# BeagleQ-v03_1.net
KiCad netlist of a schematic drawn in EAGLE
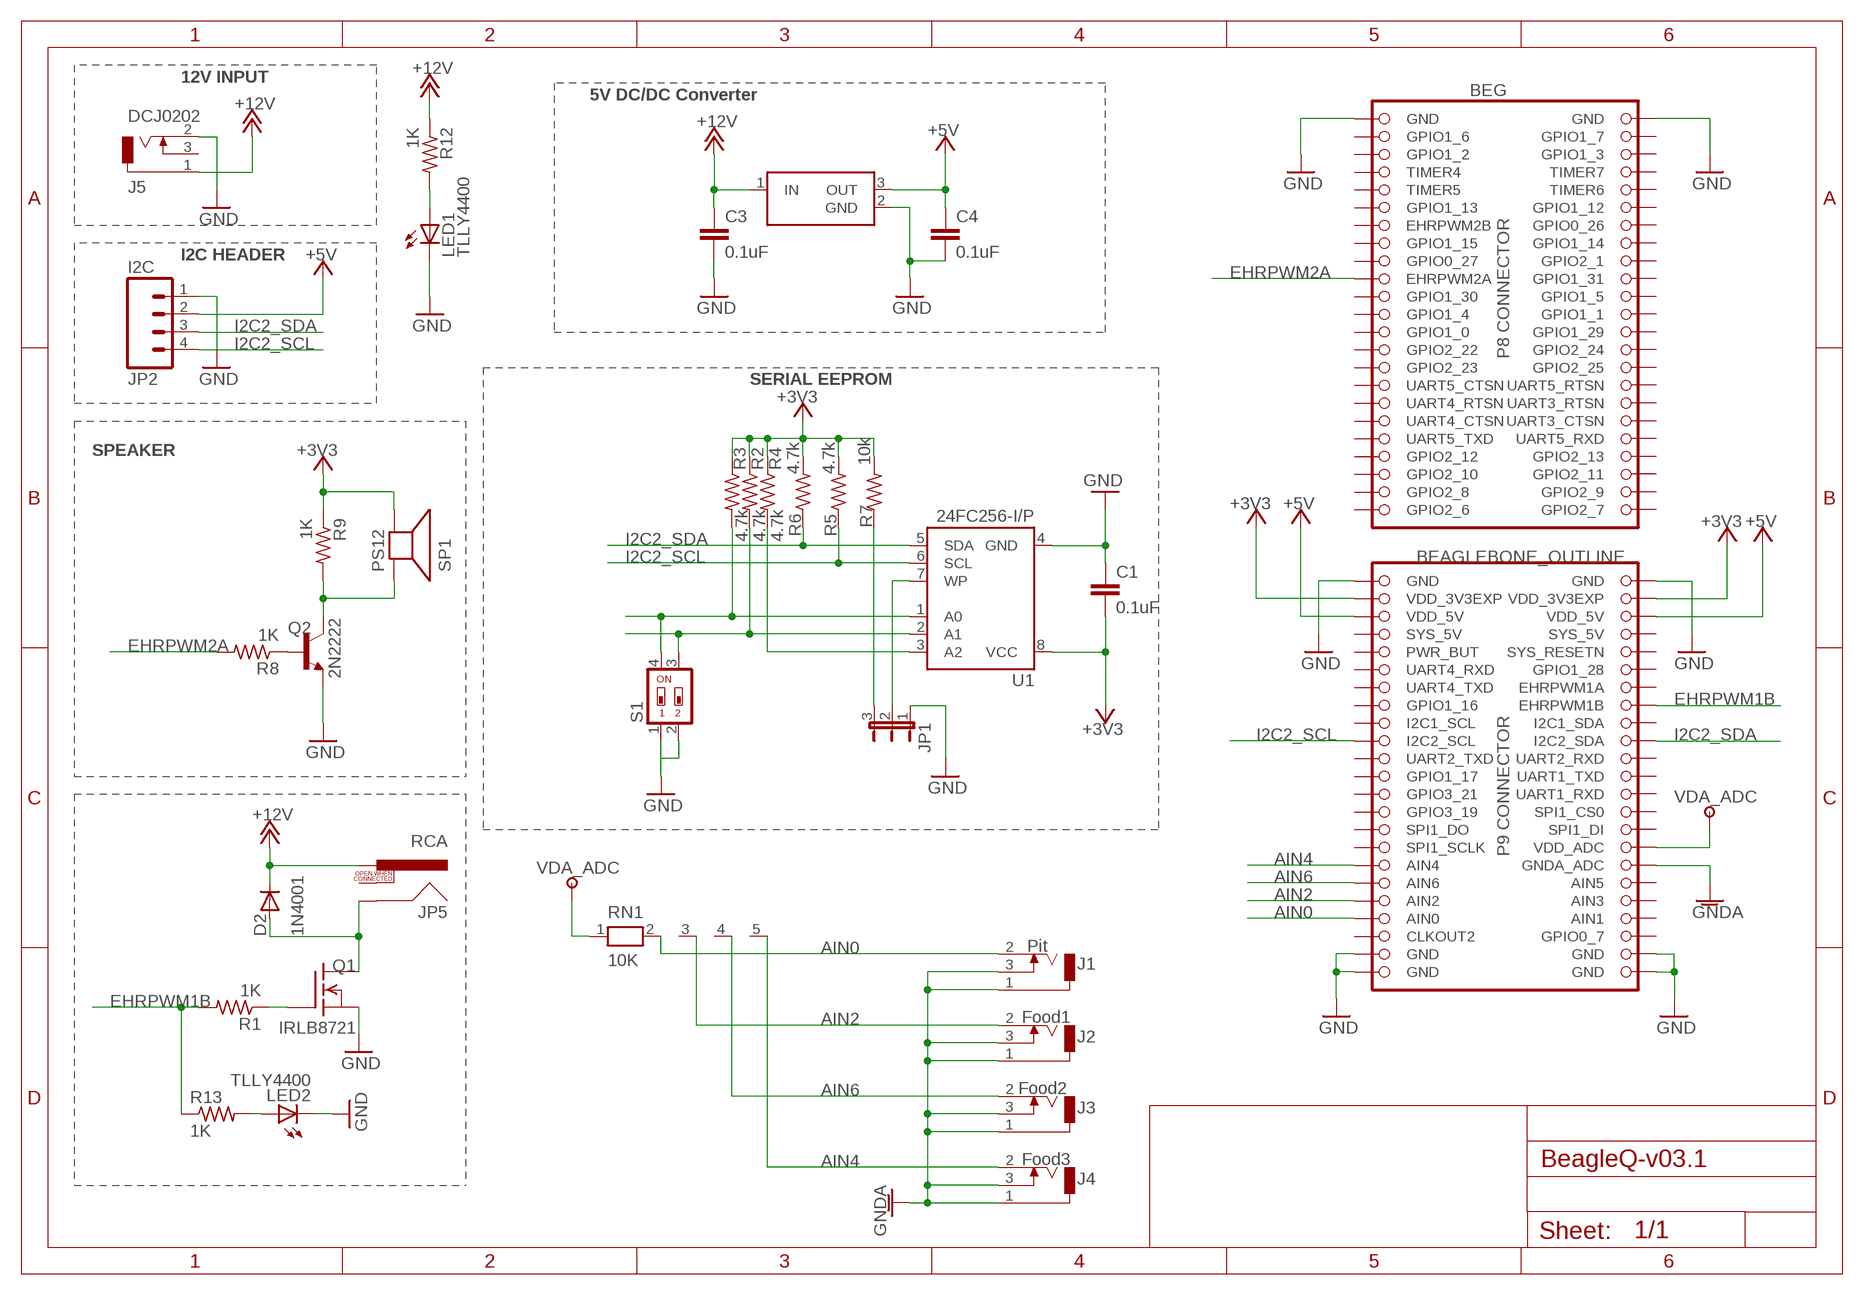
[diagram p0: schematic, sheet 1]

(export (version "E")
  (design (tool "Eeschema 10.0.6"))
  (components
    (comp (ref "BEG")
      (value "BEAGLEBONE_OUTLINE")
      (footprint "eagle-import:BEAGLEBONE_SHIELD")
      (libsource (lib "eagle-import") (part "BEAGLEBONE_OUTLINE"))
    )
    (comp (ref "C1")
      (value "0.1uF")
      (footprint "eagle-import:C2.5-2")
      (libsource (lib "eagle-import") (part "C2.5/2"))
    )
    (comp (ref "C3")
      (value "0.1uF")
      (footprint "eagle-import:C2.5-2")
      (libsource (lib "eagle-import") (part "C2.5/2"))
    )
    (comp (ref "C4")
      (value "0.1uF")
      (footprint "eagle-import:C2.5-2")
      (libsource (lib "eagle-import") (part "C2.5/2"))
    )
    (comp (ref "D2")
      (value "1N4001")
      (footprint "eagle-import:DO41-10")
      (libsource (lib "eagle-import") (part "1N4004"))
    )
    (comp (ref "J1")
      (value "Pit")
      (footprint "eagle-import:MJ-2508N")
      (libsource (lib "eagle-import") (part "MJ-2508N"))
    )
    (comp (ref "J2")
      (value "Food1")
      (footprint "eagle-import:MJ-2508N")
      (libsource (lib "eagle-import") (part "MJ-2508N"))
    )
    (comp (ref "J3")
      (value "Food2")
      (footprint "eagle-import:MJ-2508N")
      (libsource (lib "eagle-import") (part "MJ-2508N"))
    )
    (comp (ref "J4")
      (value "Food3")
      (footprint "eagle-import:MJ-2508N")
      (libsource (lib "eagle-import") (part "MJ-2508N"))
    )
    (comp (ref "J5")
      (value "DCJ0202")
      (footprint "eagle-import:DCJ0202")
      (libsource (lib "eagle-import") (part "DCJ0202"))
    )
    (comp (ref "JP1")
      (value "WP")
      (footprint "eagle-import:JP2")
      (libsource (lib "eagle-import") (part "JP2E"))
    )
    (comp (ref "JP2")
      (value "I2C")
      (footprint "eagle-import:1X04")
      (libsource (lib "eagle-import") (part "M04PTH"))
    )
    (comp (ref "JP5")
      (value "RCA")
      (footprint "eagle-import:RCA")
      (libsource (lib "eagle-import") (part "RCA"))
    )
    (comp (ref "LED1")
      (value "TLLY4400")
      (footprint "eagle-import:LED3MM")
      (fields (field (name "MF") "VISHAY SEMICONDUCTOR"))
      (libsource (lib "eagle-import") (part "led_TLLY4400"))
    )
    (comp (ref "LED2")
      (value "TLLY4400")
      (footprint "eagle-import:LED3MM")
      (fields (field (name "MF") "VISHAY SEMICONDUCTOR"))
      (libsource (lib "eagle-import") (part "TLLY4400"))
    )
    (comp (ref "Q1")
      (value "IRLB8721")
      (footprint "eagle-import:TO220")
      (libsource (lib "eagle-import") (part "BUZ10"))
    )
    (comp (ref "Q2")
      (value "2N2222")
      (footprint "eagle-import:TO18")
      (libsource (lib "eagle-import") (part "2N2222"))
    )
    (comp (ref "R1")
      (value "1K")
      (footprint "eagle-import:0207_10")
      (libsource (lib "eagle-import") (part "R-US_0207/10"))
    )
    (comp (ref "R2")
      (value "4.7k")
      (footprint "eagle-import:0207_10")
      (libsource (lib "eagle-import") (part "resistor_R-US_0207/10"))
    )
    (comp (ref "R3")
      (value "4.7k")
      (footprint "eagle-import:0207_10")
      (libsource (lib "eagle-import") (part "resistor_R-US_0207/10"))
    )
    (comp (ref "R4")
      (value "4.7k")
      (footprint "eagle-import:0207_10")
      (libsource (lib "eagle-import") (part "resistor_R-US_0207/10"))
    )
    (comp (ref "R5")
      (value "4.7k")
      (footprint "eagle-import:0207_10")
      (libsource (lib "eagle-import") (part "resistor_R-US_0207/10"))
    )
    (comp (ref "R6")
      (value "4.7k")
      (footprint "eagle-import:0207_10")
      (libsource (lib "eagle-import") (part "resistor_R-US_0207/10"))
    )
    (comp (ref "R7")
      (value "10k")
      (footprint "eagle-import:0207_10")
      (libsource (lib "eagle-import") (part "resistor_R-US_0207/10"))
    )
    (comp (ref "R8")
      (value "1K")
      (footprint "eagle-import:0207_10")
      (libsource (lib "eagle-import") (part "R-US_0207/10"))
    )
    (comp (ref "R9")
      (value "1K")
      (footprint "eagle-import:0207_10")
      (libsource (lib "eagle-import") (part "R-US_0207/10"))
    )
    (comp (ref "R12")
      (value "1K")
      (footprint "eagle-import:0207_10")
      (libsource (lib "eagle-import") (part "resistor_R-US_0207/10"))
    )
    (comp (ref "R13")
      (value "1K")
      (footprint "eagle-import:0207_10")
      (libsource (lib "eagle-import") (part "resistor_R-US_0207/10"))
    )
    (comp (ref "RN1")
      (value "10K")
      (footprint "eagle-import:RN-5")
      (libsource (lib "eagle-import") (part "RN04"))
    )
    (comp (ref "S1")
      (value "SWS002")
      (footprint "eagle-import:SMS-002")
      (libsource (lib "eagle-import") (part "SWS002"))
    )
    (comp (ref "SP1")
      (value "PS12")
      (footprint "eagle-import:PS12")
      (libsource (lib "eagle-import") (part "SPEAKER/PS12"))
    )
    (comp (ref "U1")
      (value "24FC256-I/P")
      (footprint "eagle-import:DIL08")
      (fields (field (name "MPN") "AT24C1024BW-SH-B"))
      (libsource (lib "eagle-import") (part "AT24CP"))
    )
    (comp (ref "U2")
      (value "OKI-78SR")
      (footprint "eagle-import:OKI-78SR")
      (libsource (lib "eagle-import") (part "OKI-78SR"))
    )
  )
  (nets
    (net (code "1") (name "+3V3") (class "Default")
      (node (ref "BEG") (pin "49") (pinfunction "VDD_3V3EXP_49") (pintype "power_in"))
      (node (ref "BEG") (pin "50") (pinfunction "VDD_3V3EXP_50") (pintype "power_in"))
      (node (ref "C1") (pin "2") (pinfunction "2_2") (pintype "passive"))
      (node (ref "R2") (pin "1") (pinfunction "1_1") (pintype "passive"))
      (node (ref "R3") (pin "1") (pinfunction "1_1") (pintype "passive"))
      (node (ref "R4") (pin "1") (pinfunction "1_1") (pintype "passive"))
      (node (ref "R5") (pin "2") (pinfunction "2_2") (pintype "passive"))
      (node (ref "R6") (pin "2") (pinfunction "2_2") (pintype "passive"))
      (node (ref "R7") (pin "2") (pinfunction "2_2") (pintype "passive"))
      (node (ref "R9") (pin "1") (pinfunction "1_1") (pintype "passive"))
      (node (ref "SP1") (pin "P$2") (pinfunction "-_P$2") (pintype "passive"))
      (node (ref "U1") (pin "8") (pinfunction "VCC_8") (pintype "power_in"))
    )
    (net (code "2") (name "+5V") (class "Default")
      (node (ref "BEG") (pin "51") (pinfunction "VDD_5V_51") (pintype "power_in"))
      (node (ref "BEG") (pin "52") (pinfunction "VDD_5V_52") (pintype "power_in"))
      (node (ref "C4") (pin "1") (pinfunction "1_1") (pintype "passive"))
      (node (ref "JP2") (pin "2") (pinfunction "2_2") (pintype "passive"))
      (node (ref "U2") (pin "3") (pinfunction "OUT_3") (pintype "passive"))
    )
    (net (code "3") (name "+12V") (class "Default")
      (node (ref "C3") (pin "1") (pinfunction "1_1") (pintype "passive"))
      (node (ref "D2") (pin "C") (pinfunction "C_C") (pintype "passive"))
      (node (ref "J5") (pin "1") (pinfunction "1_1") (pintype "passive"))
      (node (ref "JP5") (pin "PIN") (pinfunction "PIN_PIN") (pintype "bidirectional"))
      (node (ref "R12") (pin "1") (pinfunction "1_1") (pintype "passive"))
      (node (ref "U2") (pin "1") (pinfunction "IN_1") (pintype "passive"))
    )
    (net (code "4") (name "/AIN0") (class "Default")
      (node (ref "BEG") (pin "85") (pinfunction "AIN0_85") (pintype "power_in"))
      (node (ref "J1") (pin "2") (pinfunction "2_2") (pintype "passive"))
      (node (ref "RN1") (pin "2") (pinfunction "2_2") (pintype "passive"))
    )
    (net (code "5") (name "/AIN2") (class "Default")
      (node (ref "BEG") (pin "83") (pinfunction "AIN2_83") (pintype "passive"))
      (node (ref "J2") (pin "2") (pinfunction "2_2") (pintype "passive"))
      (node (ref "RN1") (pin "3") (pinfunction "3_3") (pintype "passive"))
    )
    (net (code "6") (name "/AIN4") (class "Default")
      (node (ref "BEG") (pin "79") (pinfunction "AIN4_79") (pintype "passive"))
      (node (ref "J4") (pin "2") (pinfunction "2_2") (pintype "passive"))
      (node (ref "RN1") (pin "5") (pinfunction "5_5") (pintype "passive"))
    )
    (net (code "7") (name "/AIN6") (class "Default")
      (node (ref "BEG") (pin "81") (pinfunction "AIN6_81") (pintype "passive"))
      (node (ref "J3") (pin "2") (pinfunction "2_2") (pintype "passive"))
      (node (ref "RN1") (pin "4") (pinfunction "4_4") (pintype "passive"))
    )
    (net (code "8") (name "/EHRPWM1B") (class "Default")
      (node (ref "BEG") (pin "62") (pinfunction "EHRPWM1B_62") (pintype "passive"))
      (node (ref "R1") (pin "2") (pinfunction "2_2") (pintype "passive"))
      (node (ref "R13") (pin "1") (pinfunction "1_1") (pintype "passive"))
    )
    (net (code "9") (name "/EHRPWM2A") (class "Default")
      (node (ref "BEG") (pin "19") (pinfunction "EHRPWM2A_19") (pintype "passive"))
      (node (ref "R8") (pin "2") (pinfunction "2_2") (pintype "passive"))
    )
    (net (code "10") (name "/I2C2_SCL") (class "Default")
      (node (ref "BEG") (pin "65") (pinfunction "I2C2_SCL_65") (pintype "passive"))
      (node (ref "JP2") (pin "4") (pinfunction "4_4") (pintype "passive"))
      (node (ref "R5") (pin "1") (pinfunction "1_1") (pintype "passive"))
      (node (ref "U1") (pin "6") (pinfunction "SCL_6") (pintype "bidirectional"))
    )
    (net (code "11") (name "/I2C2_SDA") (class "Default")
      (node (ref "BEG") (pin "66") (pinfunction "I2C2_SDA_66") (pintype "passive"))
      (node (ref "JP2") (pin "3") (pinfunction "3_3") (pintype "passive"))
      (node (ref "R6") (pin "1") (pinfunction "1_1") (pintype "passive"))
      (node (ref "U1") (pin "5") (pinfunction "SDA_5") (pintype "bidirectional"))
    )
    (net (code "12") (name "/SYS_5V") (class "Default")
      (node (ref "BEG") (pin "53") (pinfunction "SYS_5V_53") (pintype "power_in"))
    )
    (net (code "13") (name "GND") (class "Default")
      (node (ref "BEG") (pin "1") (pinfunction "GND_1") (pintype "power_in"))
      (node (ref "BEG") (pin "2") (pinfunction "GND_2") (pintype "power_in"))
      (node (ref "BEG") (pin "47") (pinfunction "GND_47") (pintype "power_in"))
      (node (ref "BEG") (pin "48") (pinfunction "GND_48") (pintype "power_in"))
      (node (ref "BEG") (pin "89") (pinfunction "GND_89") (pintype "power_in"))
      (node (ref "BEG") (pin "90") (pinfunction "GND_90") (pintype "power_in"))
      (node (ref "BEG") (pin "91") (pinfunction "GND_91") (pintype "power_in"))
      (node (ref "BEG") (pin "92") (pinfunction "GND_92") (pintype "power_in"))
      (node (ref "C1") (pin "1") (pinfunction "1_1") (pintype "passive"))
      (node (ref "C3") (pin "2") (pinfunction "2_2") (pintype "passive"))
      (node (ref "C4") (pin "2") (pinfunction "2_2") (pintype "passive"))
      (node (ref "J5") (pin "2") (pinfunction "3_2") (pintype "passive"))
      (node (ref "JP1") (pin "1") (pinfunction "1_1") (pintype "passive"))
      (node (ref "JP2") (pin "1") (pinfunction "1_1") (pintype "passive"))
      (node (ref "LED1") (pin "K") (pinfunction "C_K") (pintype "passive"))
      (node (ref "LED2") (pin "K") (pinfunction "C_K") (pintype "passive"))
      (node (ref "Q1") (pin "3") (pinfunction "S_3") (pintype "passive"))
      (node (ref "Q1") (pin "4") (pinfunction "S_4") (pintype "passive"))
      (node (ref "Q2") (pin "1") (pinfunction "E_1") (pintype "passive"))
      (node (ref "S1") (pin "1") (pinfunction "1_1") (pintype "passive"))
      (node (ref "S1") (pin "2") (pinfunction "2_2") (pintype "passive"))
      (node (ref "U1") (pin "4") (pinfunction "GND_4") (pintype "power_in"))
      (node (ref "U2") (pin "2") (pinfunction "GND_2") (pintype "passive"))
    )
    (net (code "14") (name "GNDA") (class "Default")
      (node (ref "BEG") (pin "80") (pinfunction "GNDA_ADC_80") (pintype "passive"))
      (node (ref "J1") (pin "1") (pinfunction "1_1") (pintype "passive"))
      (node (ref "J1") (pin "3") (pinfunction "3_3") (pintype "passive"))
      (node (ref "J2") (pin "1") (pinfunction "1_1") (pintype "passive"))
      (node (ref "J2") (pin "3") (pinfunction "3_3") (pintype "passive"))
      (node (ref "J3") (pin "1") (pinfunction "1_1") (pintype "passive"))
      (node (ref "J3") (pin "3") (pinfunction "3_3") (pintype "passive"))
      (node (ref "J4") (pin "1") (pinfunction "1_1") (pintype "passive"))
      (node (ref "J4") (pin "3") (pinfunction "3_3") (pintype "passive"))
    )
    (net (code "15") (name "Net-(JP1-Pad3)") (class "Default")
      (node (ref "JP1") (pin "3") (pinfunction "3_3") (pintype "passive"))
      (node (ref "R7") (pin "1") (pinfunction "1_1") (pintype "passive"))
    )
    (net (code "16") (name "Net-(LED1-PadA)") (class "Default")
      (node (ref "LED1") (pin "A") (pinfunction "A_A") (pintype "passive"))
      (node (ref "R12") (pin "2") (pinfunction "2_2") (pintype "passive"))
    )
    (net (code "17") (name "Net-(LED2-PadA)") (class "Default")
      (node (ref "LED2") (pin "A") (pinfunction "A_A") (pintype "passive"))
      (node (ref "R13") (pin "2") (pinfunction "2_2") (pintype "passive"))
    )
    (net (code "18") (name "Net-(Q1-D)") (class "Default")
      (node (ref "D2") (pin "A") (pinfunction "A_A") (pintype "passive"))
      (node (ref "JP5") (pin "SHELL") (pinfunction "SHELL_SHELL") (pintype "bidirectional"))
      (node (ref "Q1") (pin "2") (pinfunction "D_2") (pintype "passive"))
    )
    (net (code "19") (name "Net-(Q1-G)") (class "Default")
      (node (ref "Q1") (pin "1") (pinfunction "G_1") (pintype "passive"))
      (node (ref "R1") (pin "1") (pinfunction "1_1") (pintype "passive"))
    )
    (net (code "20") (name "Net-(Q2-B)") (class "Default")
      (node (ref "Q2") (pin "2") (pinfunction "B_2") (pintype "passive"))
      (node (ref "R8") (pin "1") (pinfunction "1_1") (pintype "passive"))
    )
    (net (code "21") (name "Net-(Q2-C)") (class "Default")
      (node (ref "Q2") (pin "3") (pinfunction "C_3") (pintype "passive"))
      (node (ref "R9") (pin "2") (pinfunction "2_2") (pintype "passive"))
      (node (ref "SP1") (pin "P$1") (pinfunction "+_P$1") (pintype "passive"))
    )
    (net (code "22") (name "Net-(U1-A0)") (class "Default")
      (node (ref "R3") (pin "2") (pinfunction "2_2") (pintype "passive"))
      (node (ref "S1") (pin "4") (pinfunction "4_4") (pintype "passive"))
      (node (ref "U1") (pin "1") (pinfunction "A0_1") (pintype "input"))
    )
    (net (code "23") (name "Net-(U1-A1)") (class "Default")
      (node (ref "R2") (pin "2") (pinfunction "2_2") (pintype "passive"))
      (node (ref "S1") (pin "3") (pinfunction "3_3") (pintype "passive"))
      (node (ref "U1") (pin "2") (pinfunction "A1_2") (pintype "input"))
    )
    (net (code "24") (name "Net-(U1-A2)") (class "Default")
      (node (ref "R4") (pin "2") (pinfunction "2_2") (pintype "passive"))
      (node (ref "U1") (pin "3") (pinfunction "A2_3") (pintype "input"))
    )
    (net (code "25") (name "Net-(U1-WP)") (class "Default")
      (node (ref "JP1") (pin "2") (pinfunction "2_2") (pintype "passive"))
      (node (ref "U1") (pin "7") (pinfunction "WP_7") (pintype "input"))
    )
    (net (code "26") (name "VDA_ADC") (class "Default")
      (node (ref "BEG") (pin "78") (pinfunction "VDD_ADC_78") (pintype "passive"))
      (node (ref "RN1") (pin "1") (pinfunction "1_1") (pintype "passive"))
    )
    (net (code "27") (name "unconnected-(BEG-AIN1-Pad86)") (class "Default")
      (node (ref "BEG") (pin "86") (pinfunction "AIN1_86") (pintype "passive"))
    )
    (net (code "28") (name "unconnected-(BEG-AIN3-Pad84)") (class "Default")
      (node (ref "BEG") (pin "84") (pinfunction "AIN3_84") (pintype "passive"))
    )
    (net (code "29") (name "unconnected-(BEG-AIN5-Pad82)") (class "Default")
      (node (ref "BEG") (pin "82") (pinfunction "AIN5_82") (pintype "passive"))
    )
    (net (code "30") (name "unconnected-(BEG-CLKOUT2-Pad87)") (class "Default")
      (node (ref "BEG") (pin "87") (pinfunction "CLKOUT2_87") (pintype "input"))
    )
    (net (code "31") (name "unconnected-(BEG-EHRPWM1A-Pad60)") (class "Default")
      (node (ref "BEG") (pin "60") (pinfunction "EHRPWM1A_60") (pintype "passive"))
    )
    (net (code "32") (name "unconnected-(BEG-EHRPWM2B-Pad13)") (class "Default")
      (node (ref "BEG") (pin "13") (pinfunction "EHRPWM2B_13") (pintype "passive"))
    )
    (net (code "33") (name "unconnected-(BEG-GPIO0_7-Pad88)") (class "Default")
      (node (ref "BEG") (pin "88") (pinfunction "GPIO0_7_88") (pintype "passive"))
    )
    (net (code "34") (name "unconnected-(BEG-GPIO0_26-Pad14)") (class "Default")
      (node (ref "BEG") (pin "14") (pinfunction "GPIO0_26_14") (pintype "passive"))
    )
    (net (code "35") (name "unconnected-(BEG-GPIO0_27-Pad17)") (class "Default")
      (node (ref "BEG") (pin "17") (pinfunction "GPIO0_27_17") (pintype "passive"))
    )
    (net (code "36") (name "unconnected-(BEG-GPIO1_0-Pad25)") (class "Default")
      (node (ref "BEG") (pin "25") (pinfunction "GPIO1_0_25") (pintype "passive"))
    )
    (net (code "37") (name "unconnected-(BEG-GPIO1_1-Pad24)") (class "Default")
      (node (ref "BEG") (pin "24") (pinfunction "GPIO1_1_24") (pintype "passive"))
    )
    (net (code "38") (name "unconnected-(BEG-GPIO1_2-Pad5)") (class "Default")
      (node (ref "BEG") (pin "5") (pinfunction "GPIO1_2_5") (pintype "passive"))
    )
    (net (code "39") (name "unconnected-(BEG-GPIO1_3-Pad6)") (class "Default")
      (node (ref "BEG") (pin "6") (pinfunction "GPIO1_3_6") (pintype "passive"))
    )
    (net (code "40") (name "unconnected-(BEG-GPIO1_4-Pad23)") (class "Default")
      (node (ref "BEG") (pin "23") (pinfunction "GPIO1_4_23") (pintype "passive"))
    )
    (net (code "41") (name "unconnected-(BEG-GPIO1_5-Pad22)") (class "Default")
      (node (ref "BEG") (pin "22") (pinfunction "GPIO1_5_22") (pintype "passive"))
    )
    (net (code "42") (name "unconnected-(BEG-GPIO1_6-Pad3)") (class "Default")
      (node (ref "BEG") (pin "3") (pinfunction "GPIO1_6_3") (pintype "passive"))
    )
    (net (code "43") (name "unconnected-(BEG-GPIO1_7-Pad4)") (class "Default")
      (node (ref "BEG") (pin "4") (pinfunction "GPIO1_7_4") (pintype "passive"))
    )
    (net (code "44") (name "unconnected-(BEG-GPIO1_12-Pad12)") (class "Default")
      (node (ref "BEG") (pin "12") (pinfunction "GPIO1_12_12") (pintype "passive"))
    )
    (net (code "45") (name "unconnected-(BEG-GPIO1_13-Pad11)") (class "Default")
      (node (ref "BEG") (pin "11") (pinfunction "GPIO1_13_11") (pintype "passive"))
    )
    (net (code "46") (name "unconnected-(BEG-GPIO1_14-Pad16)") (class "Default")
      (node (ref "BEG") (pin "16") (pinfunction "GPIO1_14_16") (pintype "passive"))
    )
    (net (code "47") (name "unconnected-(BEG-GPIO1_15-Pad15)") (class "Default")
      (node (ref "BEG") (pin "15") (pinfunction "GPIO1_15_15") (pintype "passive"))
    )
    (net (code "48") (name "unconnected-(BEG-GPIO1_16-Pad61)") (class "Default")
      (node (ref "BEG") (pin "61") (pinfunction "GPIO1_16_61") (pintype "passive"))
    )
    (net (code "49") (name "unconnected-(BEG-GPIO1_17-Pad69)") (class "Default")
      (node (ref "BEG") (pin "69") (pinfunction "GPIO1_17_69") (pintype "passive"))
    )
    (net (code "50") (name "unconnected-(BEG-GPIO1_28-Pad58)") (class "Default")
      (node (ref "BEG") (pin "58") (pinfunction "GPIO1_28_58") (pintype "passive"))
    )
    (net (code "51") (name "unconnected-(BEG-GPIO1_29-Pad26)") (class "Default")
      (node (ref "BEG") (pin "26") (pinfunction "GPIO1_29_26") (pintype "passive"))
    )
    (net (code "52") (name "unconnected-(BEG-GPIO1_30-Pad21)") (class "Default")
      (node (ref "BEG") (pin "21") (pinfunction "GPIO1_30_21") (pintype "passive"))
    )
    (net (code "53") (name "unconnected-(BEG-GPIO1_31-Pad20)") (class "Default")
      (node (ref "BEG") (pin "20") (pinfunction "GPIO1_31_20") (pintype "passive"))
    )
    (net (code "54") (name "unconnected-(BEG-GPIO2_1-Pad18)") (class "Default")
      (node (ref "BEG") (pin "18") (pinfunction "GPIO2_1_18") (pintype "passive"))
    )
    (net (code "55") (name "unconnected-(BEG-GPIO2_6-Pad45)") (class "Default")
      (node (ref "BEG") (pin "45") (pinfunction "GPIO2_6_45") (pintype "passive"))
    )
    (net (code "56") (name "unconnected-(BEG-GPIO2_7-Pad46)") (class "Default")
      (node (ref "BEG") (pin "46") (pinfunction "GPIO2_7_46") (pintype "passive"))
    )
    (net (code "57") (name "unconnected-(BEG-GPIO2_8-Pad43)") (class "Default")
      (node (ref "BEG") (pin "43") (pinfunction "GPIO2_8_43") (pintype "passive"))
    )
    (net (code "58") (name "unconnected-(BEG-GPIO2_9-Pad44)") (class "Default")
      (node (ref "BEG") (pin "44") (pinfunction "GPIO2_9_44") (pintype "passive"))
    )
    (net (code "59") (name "unconnected-(BEG-GPIO2_10-Pad41)") (class "Default")
      (node (ref "BEG") (pin "41") (pinfunction "GPIO2_10_41") (pintype "passive"))
    )
    (net (code "60") (name "unconnected-(BEG-GPIO2_11-Pad42)") (class "Default")
      (node (ref "BEG") (pin "42") (pinfunction "GPIO2_11_42") (pintype "passive"))
    )
    (net (code "61") (name "unconnected-(BEG-GPIO2_12-Pad39)") (class "Default")
      (node (ref "BEG") (pin "39") (pinfunction "GPIO2_12_39") (pintype "passive"))
    )
    (net (code "62") (name "unconnected-(BEG-GPIO2_13-Pad40)") (class "Default")
      (node (ref "BEG") (pin "40") (pinfunction "GPIO2_13_40") (pintype "passive"))
    )
    (net (code "63") (name "unconnected-(BEG-GPIO2_22-Pad27)") (class "Default")
      (node (ref "BEG") (pin "27") (pinfunction "GPIO2_22_27") (pintype "passive"))
    )
    (net (code "64") (name "unconnected-(BEG-GPIO2_23-Pad29)") (class "Default")
      (node (ref "BEG") (pin "29") (pinfunction "GPIO2_23_29") (pintype "passive"))
    )
    (net (code "65") (name "unconnected-(BEG-GPIO2_24-Pad28)") (class "Default")
      (node (ref "BEG") (pin "28") (pinfunction "GPIO2_24_28") (pintype "passive"))
    )
    (net (code "66") (name "unconnected-(BEG-GPIO2_25-Pad30)") (class "Default")
      (node (ref "BEG") (pin "30") (pinfunction "GPIO2_25_30") (pintype "passive"))
    )
    (net (code "67") (name "unconnected-(BEG-GPIO3_19-Pad73)") (class "Default")
      (node (ref "BEG") (pin "73") (pinfunction "GPIO3_19_73") (pintype "passive"))
    )
    (net (code "68") (name "unconnected-(BEG-GPIO3_21-Pad71)") (class "Default")
      (node (ref "BEG") (pin "71") (pinfunction "GPIO3_21_71") (pintype "passive"))
    )
    (net (code "69") (name "unconnected-(BEG-I2C1_SCL-Pad63)") (class "Default")
      (node (ref "BEG") (pin "63") (pinfunction "I2C1_SCL_63") (pintype "passive"))
    )
    (net (code "70") (name "unconnected-(BEG-I2C1_SDA-Pad64)") (class "Default")
      (node (ref "BEG") (pin "64") (pinfunction "I2C1_SDA_64") (pintype "passive"))
    )
    (net (code "71") (name "unconnected-(BEG-PWR_BUT-Pad55)") (class "Default")
      (node (ref "BEG") (pin "55") (pinfunction "PWR_BUT_55") (pintype "passive"))
    )
    (net (code "72") (name "unconnected-(BEG-SPI1_CS0-Pad74)") (class "Default")
      (node (ref "BEG") (pin "74") (pinfunction "SPI1_CS0_74") (pintype "passive"))
    )
    (net (code "73") (name "unconnected-(BEG-SPI1_DI-Pad76)") (class "Default")
      (node (ref "BEG") (pin "76") (pinfunction "SPI1_DI_76") (pintype "passive"))
    )
    (net (code "74") (name "unconnected-(BEG-SPI1_DO-Pad75)") (class "Default")
      (node (ref "BEG") (pin "75") (pinfunction "SPI1_DO_75") (pintype "passive"))
    )
    (net (code "75") (name "unconnected-(BEG-SPI1_SCLK-Pad77)") (class "Default")
      (node (ref "BEG") (pin "77") (pinfunction "SPI1_SCLK_77") (pintype "passive"))
    )
    (net (code "76") (name "unconnected-(BEG-SYS_5V-Pad54)") (class "Default")
      (node (ref "BEG") (pin "54") (pinfunction "SYS_5V_54") (pintype "passive"))
    )
    (net (code "77") (name "unconnected-(BEG-SYS_RESETN-Pad56)") (class "Default")
      (node (ref "BEG") (pin "56") (pinfunction "SYS_RESETN_56") (pintype "passive"))
    )
    (net (code "78") (name "unconnected-(BEG-TIMER4-Pad7)") (class "Default")
      (node (ref "BEG") (pin "7") (pinfunction "TIMER4_7") (pintype "passive"))
    )
    (net (code "79") (name "unconnected-(BEG-TIMER5-Pad9)") (class "Default")
      (node (ref "BEG") (pin "9") (pinfunction "TIMER5_9") (pintype "passive"))
    )
    (net (code "80") (name "unconnected-(BEG-TIMER6-Pad10)") (class "Default")
      (node (ref "BEG") (pin "10") (pinfunction "TIMER6_10") (pintype "passive"))
    )
    (net (code "81") (name "unconnected-(BEG-TIMER7-Pad8)") (class "Default")
      (node (ref "BEG") (pin "8") (pinfunction "TIMER7_8") (pintype "passive"))
    )
    (net (code "82") (name "unconnected-(BEG-UART1_RXD-Pad72)") (class "Default")
      (node (ref "BEG") (pin "72") (pinfunction "UART1_RXD_72") (pintype "passive"))
    )
    (net (code "83") (name "unconnected-(BEG-UART1_TXD-Pad70)") (class "Default")
      (node (ref "BEG") (pin "70") (pinfunction "UART1_TXD_70") (pintype "passive"))
    )
    (net (code "84") (name "unconnected-(BEG-UART2_RXD-Pad68)") (class "Default")
      (node (ref "BEG") (pin "68") (pinfunction "UART2_RXD_68") (pintype "passive"))
    )
    (net (code "85") (name "unconnected-(BEG-UART2_TXD-Pad67)") (class "Default")
      (node (ref "BEG") (pin "67") (pinfunction "UART2_TXD_67") (pintype "passive"))
    )
    (net (code "86") (name "unconnected-(BEG-UART3_CTSN-Pad36)") (class "Default")
      (node (ref "BEG") (pin "36") (pinfunction "UART3_CTSN_36") (pintype "passive"))
    )
    (net (code "87") (name "unconnected-(BEG-UART3_RTSN-Pad34)") (class "Default")
      (node (ref "BEG") (pin "34") (pinfunction "UART3_RTSN_34") (pintype "passive"))
    )
    (net (code "88") (name "unconnected-(BEG-UART4_CTSN-Pad35)") (class "Default")
      (node (ref "BEG") (pin "35") (pinfunction "UART4_CTSN_35") (pintype "passive"))
    )
    (net (code "89") (name "unconnected-(BEG-UART4_RTSN-Pad33)") (class "Default")
      (node (ref "BEG") (pin "33") (pinfunction "UART4_RTSN_33") (pintype "passive"))
    )
    (net (code "90") (name "unconnected-(BEG-UART4_RXD-Pad57)") (class "Default")
      (node (ref "BEG") (pin "57") (pinfunction "UART4_RXD_57") (pintype "passive"))
    )
    (net (code "91") (name "unconnected-(BEG-UART4_TXD-Pad59)") (class "Default")
      (node (ref "BEG") (pin "59") (pinfunction "UART4_TXD_59") (pintype "passive"))
    )
    (net (code "92") (name "unconnected-(BEG-UART5_CTSN-Pad31)") (class "Default")
      (node (ref "BEG") (pin "31") (pinfunction "UART5_CTSN_31") (pintype "passive"))
    )
    (net (code "93") (name "unconnected-(BEG-UART5_RTSN-Pad32)") (class "Default")
      (node (ref "BEG") (pin "32") (pinfunction "UART5_RTSN_32") (pintype "passive"))
    )
    (net (code "94") (name "unconnected-(BEG-UART5_RXD-Pad38)") (class "Default")
      (node (ref "BEG") (pin "38") (pinfunction "UART5_RXD_38") (pintype "passive"))
    )
    (net (code "95") (name "unconnected-(BEG-UART5_TXD-Pad37)") (class "Default")
      (node (ref "BEG") (pin "37") (pinfunction "UART5_TXD_37") (pintype "passive"))
    )
    (net (code "96") (name "unconnected-(J5-2-Pad3)") (class "Default")
      (node (ref "J5") (pin "3") (pinfunction "2_3") (pintype "passive"))
    )
    (net (code "97") (name "unconnected-(JP5-PadSWITCH)") (class "Default")
      (node (ref "JP5") (pin "SWITCH") (pinfunction "SWITCH_SWITCH") (pintype "bidirectional"))
    )
  )
)
